# usb2rs232.net
KiCad netlist of a schematic drawn in EAGLE
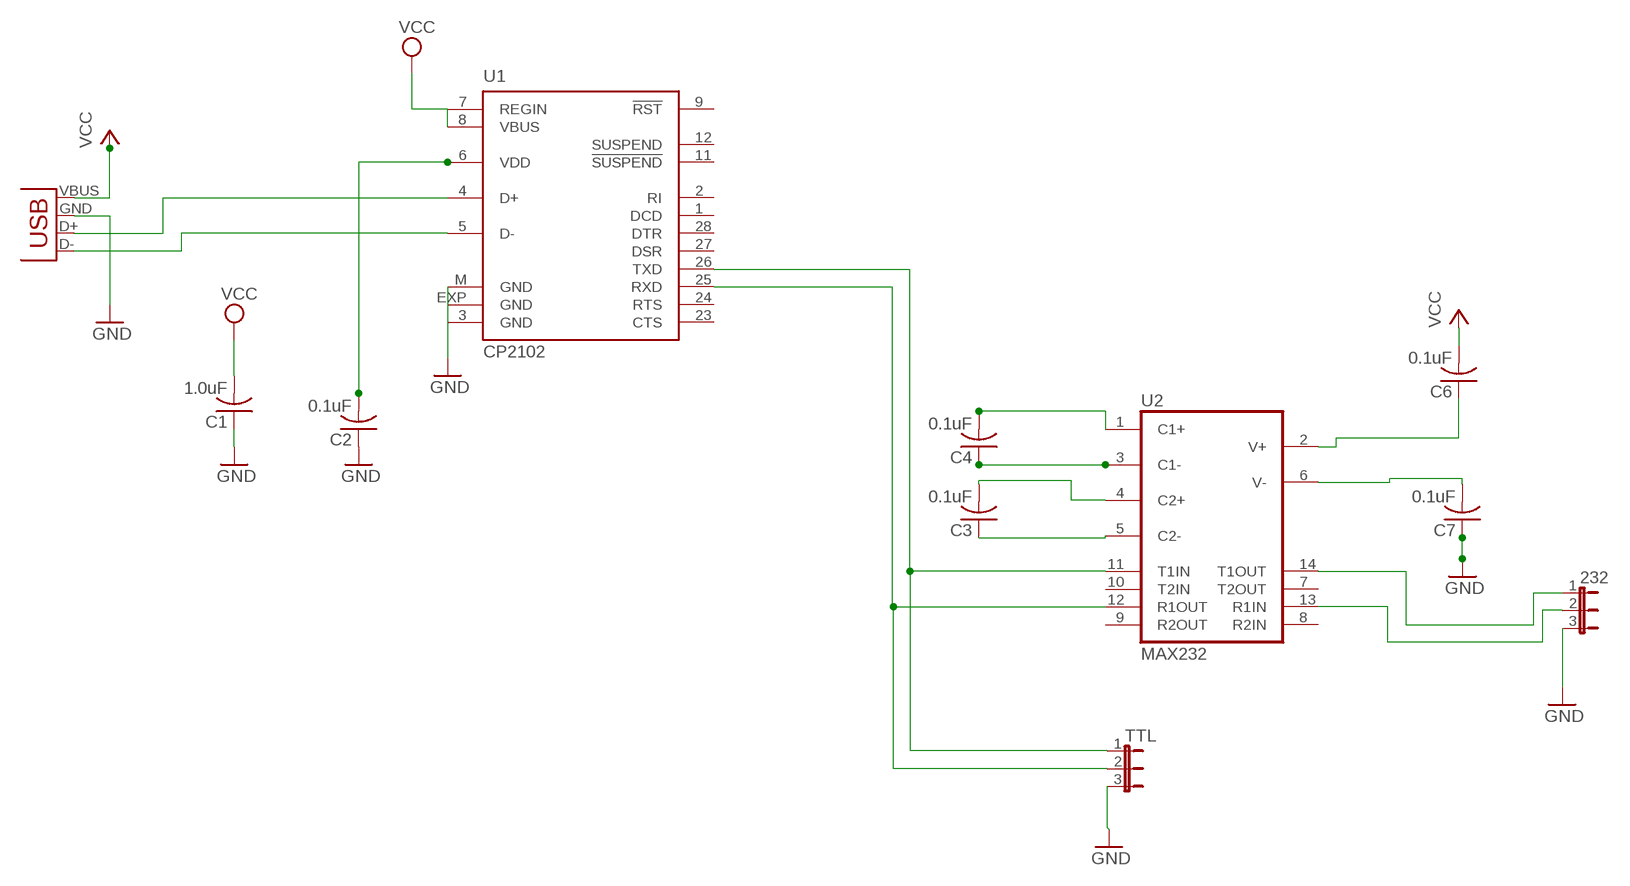
[diagram p0: schematic, sheet 1]

(export (version "E")
  (design (tool "Eeschema 10.0.6"))
  (components
    (comp (ref "232")
      (value "JP2E")
      (footprint "eagle-import:JP2")
      (libsource (lib "eagle-import") (part "JP2E"))
    )
    (comp (ref "C1")
      (value "1.0uF")
      (footprint "eagle-import:C0603")
      (libsource (lib "eagle-import") (part "C-USC0603"))
    )
    (comp (ref "C2")
      (value "0.1uF")
      (footprint "eagle-import:C0603")
      (libsource (lib "eagle-import") (part "C-USC0603"))
    )
    (comp (ref "C3")
      (value "0.1uF")
      (footprint "eagle-import:C0603")
      (libsource (lib "eagle-import") (part "C-USC0603"))
    )
    (comp (ref "C4")
      (value "0.1uF")
      (footprint "eagle-import:C0603")
      (libsource (lib "eagle-import") (part "C-USC0603"))
    )
    (comp (ref "C6")
      (value "0.1uF")
      (footprint "eagle-import:C0603")
      (libsource (lib "eagle-import") (part "C-USC0603"))
    )
    (comp (ref "C7")
      (value "0.1uF")
      (footprint "eagle-import:C0603")
      (libsource (lib "eagle-import") (part "C-USC0603"))
    )
    (comp (ref "JP3")
      (value "USB-A-H")
      (footprint "eagle-import:USB-A-H")
      (libsource (lib "eagle-import") (part "USB-A-H"))
    )
    (comp (ref "TTL")
      (value "JP2E")
      (footprint "eagle-import:JP2")
      (libsource (lib "eagle-import") (part "JP2E"))
    )
    (comp (ref "U1")
      (value "CP2102")
      (footprint "eagle-import:MLP28")
      (fields (field (name "MF") "FARNELL") (field (name "MPN") "CP2102-GM"))
      (libsource (lib "eagle-import") (part "CP2102"))
    )
    (comp (ref "U2")
      (value "MAX232")
      (footprint "eagle-import:SO16")
      (fields (field (name "MF") "MAXIM") (field (name "MPN") "MAX232ACPE+"))
      (libsource (lib "eagle-import") (part "MAX232"))
    )
  )
  (nets
    (net (code "1") (name "GND") (class "Default")
      (node (ref "232") (pin "3") (pinfunction "3_3") (pintype "passive"))
      (node (ref "C1") (pin "1") (pinfunction "1_1") (pintype "passive"))
      (node (ref "C2") (pin "1") (pinfunction "1_1") (pintype "passive"))
      (node (ref "C7") (pin "1") (pinfunction "1_1") (pintype "passive"))
      (node (ref "JP3") (pin "GND") (pinfunction "VBUS_GND") (pintype "bidirectional"))
      (node (ref "TTL") (pin "3") (pinfunction "3_3") (pintype "passive"))
      (node (ref "U1") (pin "3") (pinfunction "GND_3") (pintype "power_in"))
      (node (ref "U1") (pin "EXP") (pinfunction "GND_EXP") (pintype "power_in"))
      (node (ref "U1") (pin "M") (pinfunction "GND_M") (pintype "power_in"))
    )
    (net (code "2") (name "Net-(JP3-D+)") (class "Default")
      (node (ref "JP3") (pin "D-") (pinfunction "D+_D-") (pintype "bidirectional"))
      (node (ref "U1") (pin "5") (pinfunction "D-_5") (pintype "bidirectional"))
    )
    (net (code "3") (name "Net-(JP3-D-)") (class "Default")
      (node (ref "JP3") (pin "D+") (pinfunction "D-_D+") (pintype "bidirectional"))
      (node (ref "U1") (pin "4") (pinfunction "D+_4") (pintype "bidirectional"))
    )
    (net (code "4") (name "Net-(U1-RXD)") (class "Default")
      (node (ref "TTL") (pin "2") (pinfunction "2_2") (pintype "passive"))
      (node (ref "U1") (pin "25") (pinfunction "RXD_25") (pintype "input"))
      (node (ref "U2") (pin "12") (pinfunction "R1OUT_12") (pintype "output"))
    )
    (net (code "5") (name "Net-(U1-TXD)") (class "Default")
      (node (ref "TTL") (pin "1") (pinfunction "1_1") (pintype "passive"))
      (node (ref "U1") (pin "26") (pinfunction "TXD_26") (pintype "output"))
      (node (ref "U2") (pin "11") (pinfunction "T1IN_11") (pintype "input"))
    )
    (net (code "6") (name "Net-(U1-VDD)") (class "Default")
      (node (ref "C2") (pin "2") (pinfunction "2_2") (pintype "passive"))
      (node (ref "U1") (pin "6") (pinfunction "VDD_6") (pintype "power_in"))
    )
    (net (code "7") (name "Net-(U2A-C1+)") (class "Default")
      (node (ref "C4") (pin "2") (pinfunction "2_2") (pintype "passive"))
      (node (ref "U2") (pin "1") (pinfunction "C1+_1") (pintype "bidirectional"))
    )
    (net (code "8") (name "Net-(U2A-C1-)") (class "Default")
      (node (ref "C4") (pin "1") (pinfunction "1_1") (pintype "passive"))
      (node (ref "U2") (pin "3") (pinfunction "C1-_3") (pintype "bidirectional"))
    )
    (net (code "9") (name "Net-(U2A-C2+)") (class "Default")
      (node (ref "C3") (pin "2") (pinfunction "2_2") (pintype "passive"))
      (node (ref "U2") (pin "4") (pinfunction "C2+_4") (pintype "bidirectional"))
    )
    (net (code "10") (name "Net-(U2A-C2-)") (class "Default")
      (node (ref "C3") (pin "1") (pinfunction "1_1") (pintype "passive"))
      (node (ref "U2") (pin "5") (pinfunction "C2-_5") (pintype "bidirectional"))
    )
    (net (code "11") (name "Net-(U2A-R1IN)") (class "Default")
      (node (ref "232") (pin "2") (pinfunction "2_2") (pintype "passive"))
      (node (ref "U2") (pin "13") (pinfunction "R1IN_13") (pintype "input"))
    )
    (net (code "12") (name "Net-(U2A-T1OUT)") (class "Default")
      (node (ref "232") (pin "1") (pinfunction "1_1") (pintype "passive"))
      (node (ref "U2") (pin "14") (pinfunction "T1OUT_14") (pintype "output"))
    )
    (net (code "13") (name "Net-(U2A-V+)") (class "Default")
      (node (ref "C6") (pin "1") (pinfunction "1_1") (pintype "passive"))
      (node (ref "U2") (pin "2") (pinfunction "V+_2") (pintype "bidirectional"))
    )
    (net (code "14") (name "Net-(U2A-V-)") (class "Default")
      (node (ref "C7") (pin "2") (pinfunction "2_2") (pintype "passive"))
      (node (ref "U2") (pin "6") (pinfunction "V-_6") (pintype "bidirectional"))
    )
    (net (code "15") (name "VCC") (class "Default")
      (node (ref "C1") (pin "2") (pinfunction "2_2") (pintype "passive"))
      (node (ref "C6") (pin "2") (pinfunction "2_2") (pintype "passive"))
      (node (ref "JP3") (pin "VBUS") (pinfunction "GND_VBUS") (pintype "bidirectional"))
      (node (ref "U1") (pin "7") (pinfunction "REGIN_7") (pintype "passive"))
      (node (ref "U1") (pin "8") (pinfunction "VBUS_8") (pintype "input"))
    )
    (net (code "16") (name "unconnected-(U1-CTS-Pad23)") (class "Default")
      (node (ref "U1") (pin "23") (pinfunction "CTS_23") (pintype "input"))
    )
    (net (code "17") (name "unconnected-(U1-DCD-Pad1)") (class "Default")
      (node (ref "U1") (pin "1") (pinfunction "DCD_1") (pintype "input"))
    )
    (net (code "18") (name "unconnected-(U1-DSR-Pad27)") (class "Default")
      (node (ref "U1") (pin "27") (pinfunction "DSR_27") (pintype "input"))
    )
    (net (code "19") (name "unconnected-(U1-DTR-Pad28)") (class "Default")
      (node (ref "U1") (pin "28") (pinfunction "DTR_28") (pintype "output"))
    )
    (net (code "20") (name "unconnected-(U1-RI-Pad2)") (class "Default")
      (node (ref "U1") (pin "2") (pinfunction "RI_2") (pintype "input"))
    )
    (net (code "21") (name "unconnected-(U1-RTS-Pad24)") (class "Default")
      (node (ref "U1") (pin "24") (pinfunction "RTS_24") (pintype "output"))
    )
    (net (code "22") (name "unconnected-(U1-SUSPEND-Pad12)") (class "Default")
      (node (ref "U1") (pin "12") (pinfunction "SUSPEND_12") (pintype "output"))
    )
    (net (code "23") (name "unconnected-(U1-~{RST}-Pad9)") (class "Default")
      (node (ref "U1") (pin "9") (pinfunction "~{RST}_9") (pintype "bidirectional"))
    )
    (net (code "24") (name "unconnected-(U1-~{SUSPEND}-Pad11)") (class "Default")
      (node (ref "U1") (pin "11") (pinfunction "~{SUSPEND}_11") (pintype "output"))
    )
    (net (code "25") (name "unconnected-(U2A-R2IN-Pad8)") (class "Default")
      (node (ref "U2") (pin "8") (pinfunction "R2IN_8") (pintype "input"))
    )
    (net (code "26") (name "unconnected-(U2A-R2OUT-Pad9)") (class "Default")
      (node (ref "U2") (pin "9") (pinfunction "R2OUT_9") (pintype "output"))
    )
    (net (code "27") (name "unconnected-(U2A-T2IN-Pad10)") (class "Default")
      (node (ref "U2") (pin "10") (pinfunction "T2IN_10") (pintype "input"))
    )
    (net (code "28") (name "unconnected-(U2A-T2OUT-Pad7)") (class "Default")
      (node (ref "U2") (pin "7") (pinfunction "T2OUT_7") (pintype "output"))
    )
  )
)
